# Jacdac_Pressure_Sensor_Maker.net
KiCad netlist of a schematic drawn in EAGLE
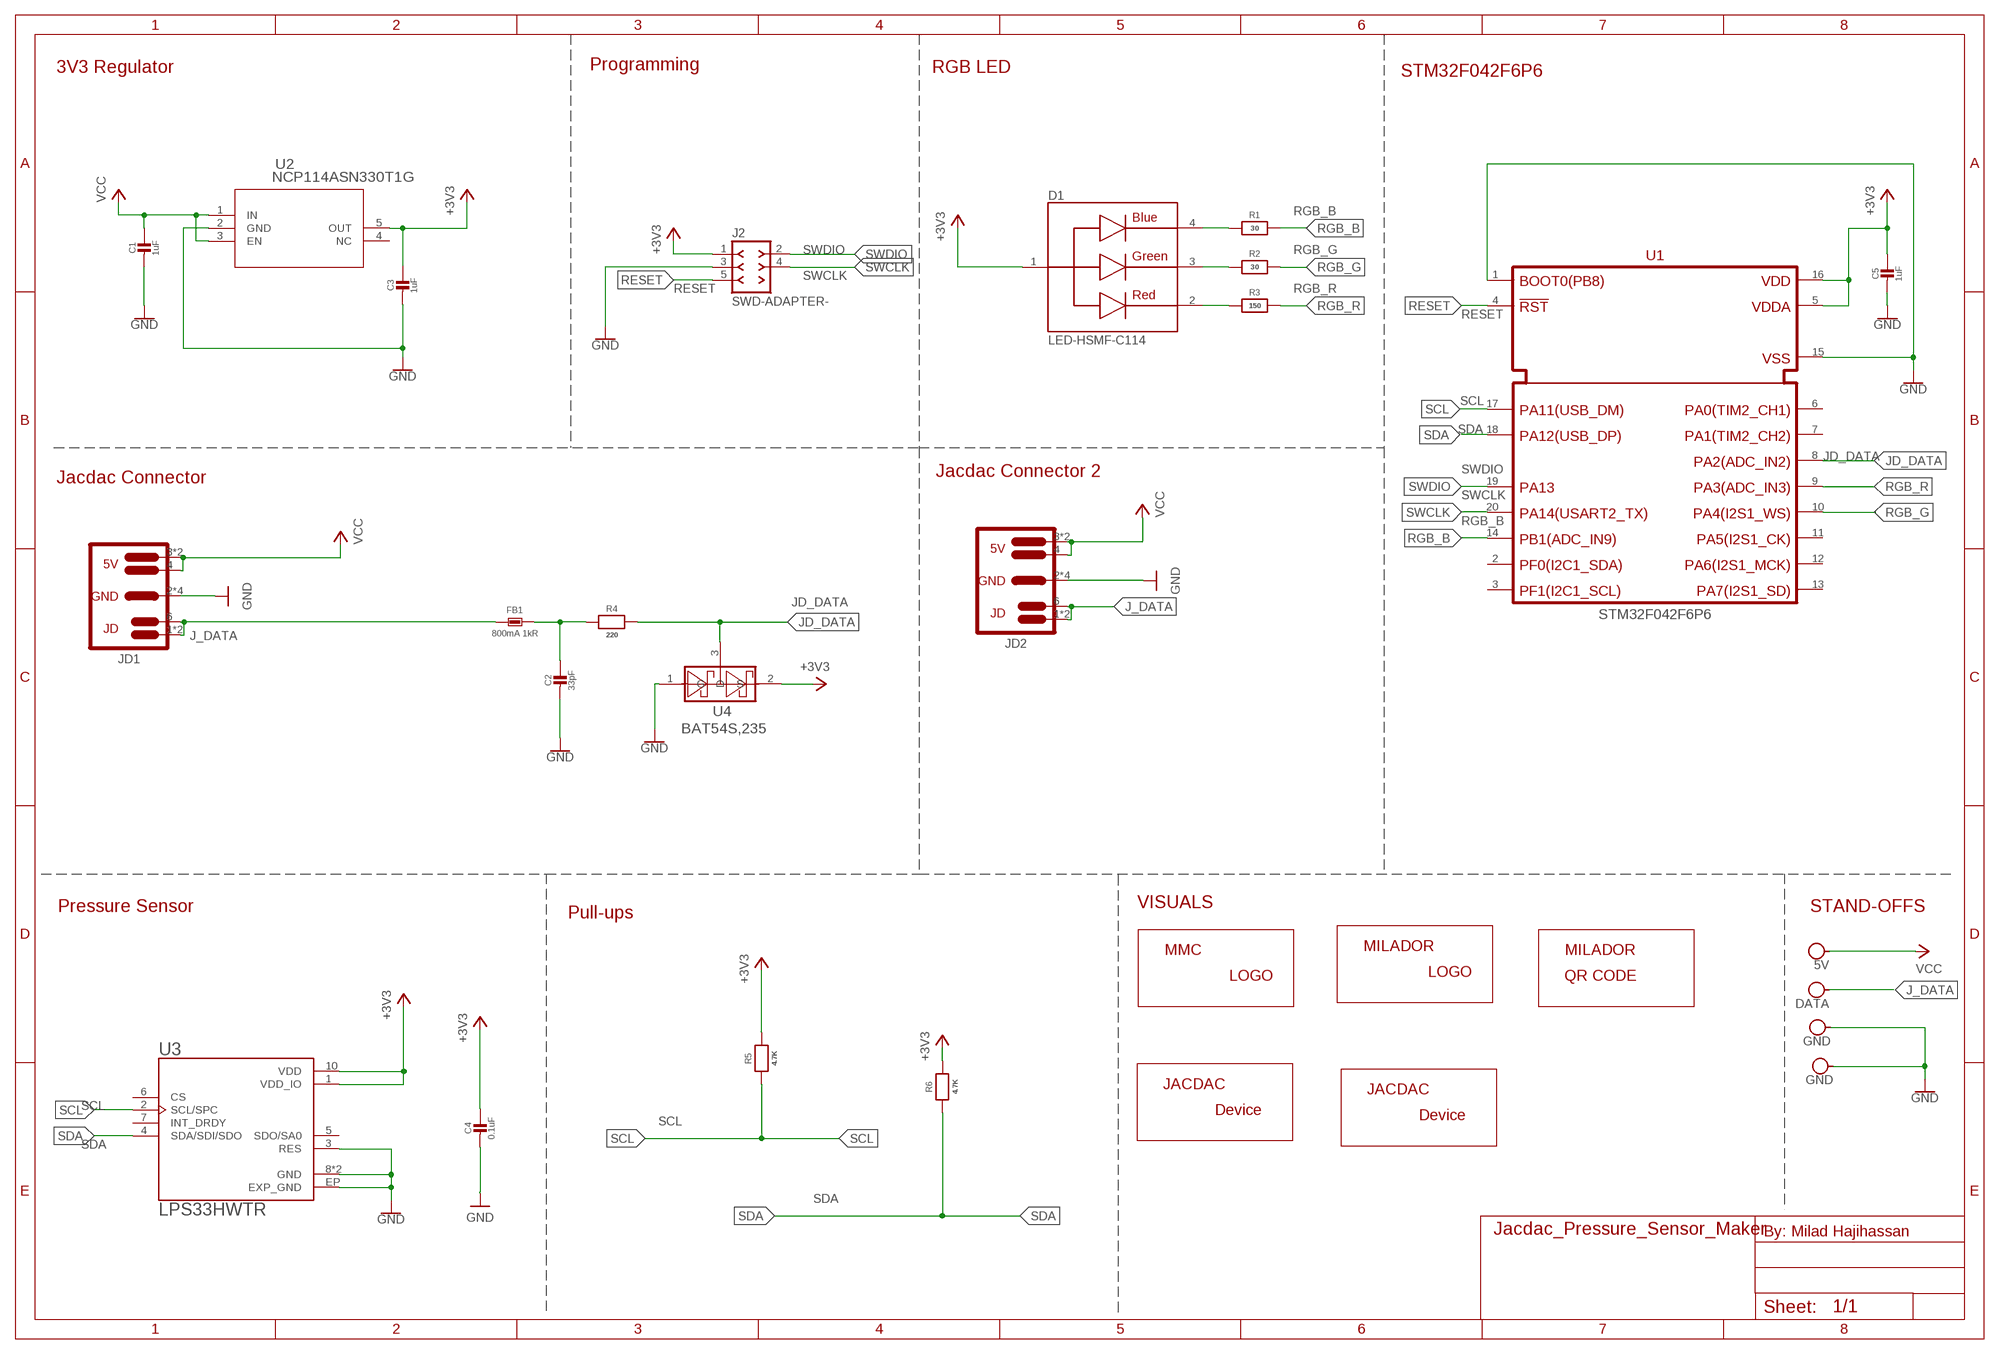
[diagram p0: schematic, sheet 1]

(export (version "E")
  (design (tool "Eeschema 10.0.6"))
  (components
    (comp (ref "C1")
      (value "1uF")
      (footprint "eagle-import:0603-NO")
      (libsource (lib "eagle-import") (part "CAP_CERAMIC-0603-NO"))
    )
    (comp (ref "C2")
      (value "33pF")
      (footprint "eagle-import:0603")
      (libsource (lib "eagle-import") (part "CAP_CERAMIC-0603"))
    )
    (comp (ref "C3")
      (value "1uF")
      (footprint "eagle-import:0603-NO")
      (libsource (lib "eagle-import") (part "CAP_CERAMIC-0603-NO"))
    )
    (comp (ref "C4")
      (value "0.1uF")
      (footprint "eagle-import:0603-NO")
      (libsource (lib "eagle-import") (part "CAP_CERAMIC-0603-NO"))
    )
    (comp (ref "C5")
      (value "1uF")
      (footprint "eagle-import:0603")
      (libsource (lib "eagle-import") (part "CAP_CERAMIC-0603"))
    )
    (comp (ref "D1")
      (value "LED-HSMF-C114")
      (footprint "eagle-import:DIOSC160X150X35-4N")
      (fields (field (name "MF") "Broadcom Limited") (field (name "MP") "HSMF-C114"))
      (libsource (lib "eagle-import") (part "LED-HSMF-C114"))
    )
    (comp (ref "FB1")
      (value "800mA 1kR")
      (footprint "eagle-import:0603-NO")
      (libsource (lib "eagle-import") (part "FERRITE-BEAD-0603-NO"))
    )
    (comp (ref "J2")
      (value "SWD-ADAPTER-")
      (footprint "eagle-import:SWD-ADAPTER")
      (libsource (lib "eagle-import") (part "SWD-ADAPTER-"))
    )
    (comp (ref "J3")
      (value "5V")
      (footprint "eagle-import:M3-HOLE-PWR-OUTL")
      (libsource (lib "eagle-import") (part "JACDAC-M3-PWR-OUTL"))
    )
    (comp (ref "J4")
      (value "DATA")
      (footprint "eagle-import:M3-HOLE-DATA-NOTCH")
      (libsource (lib "eagle-import") (part "JACDAC-M3-DATA-NOTCH"))
    )
    (comp (ref "J5")
      (value "GND")
      (footprint "eagle-import:M3-HOLE-GND")
      (libsource (lib "eagle-import") (part "JACDAC-M3-GND"))
    )
    (comp (ref "J6")
      (value "GND")
      (footprint "eagle-import:M3-HOLE-GND")
      (libsource (lib "eagle-import") (part "JACDAC-M3-GND"))
    )
    (comp (ref "JD1")
      (value "JACDAC-EDGE-OUTIE")
      (footprint "eagle-import:JD-EDGE-OUTIE")
      (libsource (lib "eagle-import") (part "JACDAC-EDGE-OUTIE"))
    )
    (comp (ref "JD2")
      (value "JACDAC-EDGE-OUTIE")
      (footprint "eagle-import:JD-EDGE-OUTIE")
      (libsource (lib "eagle-import") (part "JACDAC-EDGE-OUTIE"))
    )
    (comp (ref "LABEL_JACDAC_PS")
      (value "MILADOR-JACDAC-DEVICE-PS")
      (footprint "eagle-import:JACDAC-PRESSURE-SENSOR")
      (libsource (lib "eagle-import") (part "MILADOR-JACDAC-DEVICE-PS"))
    )
    (comp (ref "LABEL_LPS33HW")
      (value "MILADOR-JACDAC-DEVICE-LPS33HW")
      (footprint "eagle-import:JACDAC-LPS33HW")
      (libsource (lib "eagle-import") (part "MILADOR-JACDAC-DEVICE-LPS33HW"))
    )
    (comp (ref "LABEL_MILADOR")
      (value "MILADOR-LOGO-")
      (footprint "eagle-import:MILADOR_LOGO1")
      (libsource (lib "eagle-import") (part "MILADOR-LOGO-"))
    )
    (comp (ref "LABEL_QR_CODE")
      (value "MILADOR-QR-CODE-JACDAC-GITHUB-PS")
      (footprint "eagle-import:MILADOR_QR_JACDAC_PS")
      (libsource (lib "eagle-import") (part "MILADOR-QR-CODE-JACDAC-GITHUB-PS"))
    )
    (comp (ref "MMC_LOGO")
      (value "MMC_LOGO-XSM")
      (footprint "eagle-import:MMC_X-SMALL_LOGO")
      (libsource (lib "eagle-import") (part "MMC_LOGO-XSM"))
    )
    (comp (ref "R1")
      (value "30")
      (footprint "eagle-import:0603")
      (libsource (lib "eagle-import") (part "RESISTOR-0603"))
    )
    (comp (ref "R2")
      (value "30")
      (footprint "eagle-import:0603")
      (libsource (lib "eagle-import") (part "RESISTOR-0603"))
    )
    (comp (ref "R3")
      (value "150")
      (footprint "eagle-import:0603")
      (libsource (lib "eagle-import") (part "RESISTOR-0603"))
    )
    (comp (ref "R4")
      (value "220")
      (footprint "eagle-import:0603")
      (libsource (lib "eagle-import") (part "RESISTOR-0603"))
    )
    (comp (ref "R5")
      (value "4.7K")
      (footprint "eagle-import:0603")
      (libsource (lib "eagle-import") (part "RESISTOR-0603"))
    )
    (comp (ref "R6")
      (value "4.7K")
      (footprint "eagle-import:0603")
      (libsource (lib "eagle-import") (part "RESISTOR-0603"))
    )
    (comp (ref "U1")
      (value "STM32F042F6P6")
      (footprint "eagle-import:TSSOP20")
      (libsource (lib "eagle-import") (part "STM32F042F6P6"))
    )
    (comp (ref "U2")
      (value "NCP114ASN330T1G")
      (footprint "eagle-import:TSOP-5_ONS")
      (fields (field (name "COPYRIGHT") "Copyright (C) 2021 Ultra Librarian. All rights reserved."))
      (libsource (lib "eagle-import") (part "NCP114ASN330T1G"))
    )
    (comp (ref "U3")
      (value "LPS33HWTR")
      (footprint "eagle-import:PQFN60P330X330X290-11N")
      (fields (field (name "DIGI-KEY_PART_NUMBER") "497-17590-1-ND") (field (name "MF") "STMicroelectronics"))
      (libsource (lib "eagle-import") (part "LPS33HWTR"))
    )
    (comp (ref "U4")
      (value "BAT54S,235")
      (footprint "eagle-import:SOT23-3")
      (fields (field (name "MF") "Diodes") (field (name "MP") "BSS138-7-F"))
      (libsource (lib "eagle-import") (part "BAT54S,235"))
    )
  )
  (nets
    (net (code "1") (name "+3V3") (class "Default")
      (node (ref "C3") (pin "1") (pinfunction "1_1") (pintype "passive"))
      (node (ref "C4") (pin "1") (pinfunction "1_1") (pintype "passive"))
      (node (ref "C5") (pin "1") (pinfunction "1_1") (pintype "passive"))
      (node (ref "D1") (pin "1") (pinfunction "1_1") (pintype "passive"))
      (node (ref "J2") (pin "1") (pinfunction "VCC_1_1") (pintype "passive"))
      (node (ref "R5") (pin "2") (pinfunction "2_2") (pintype "passive"))
      (node (ref "R6") (pin "2") (pinfunction "2_2") (pintype "passive"))
      (node (ref "U1") (pin "16") (pinfunction "VDD_16") (pintype "input"))
      (node (ref "U1") (pin "5") (pinfunction "VDDA_5") (pintype "input"))
      (node (ref "U2") (pin "5") (pinfunction "OUT_5") (pintype "power_in"))
      (node (ref "U3") (pin "1") (pinfunction "VDD_IO_1") (pintype "power_in"))
      (node (ref "U3") (pin "10") (pinfunction "VDD_10") (pintype "power_in"))
      (node (ref "U4") (pin "2") (pinfunction "S_2") (pintype "passive"))
    )
    (net (code "2") (name "GND") (class "Default")
      (node (ref "C1") (pin "2") (pinfunction "2_2") (pintype "passive"))
      (node (ref "C2") (pin "2") (pinfunction "2_2") (pintype "passive"))
      (node (ref "C3") (pin "2") (pinfunction "2_2") (pintype "passive"))
      (node (ref "C4") (pin "2") (pinfunction "2_2") (pintype "passive"))
      (node (ref "C5") (pin "2") (pinfunction "2_2") (pintype "passive"))
      (node (ref "J2") (pin "3") (pinfunction "GND_3_3") (pintype "passive"))
      (node (ref "J5") (pin "H") (pinfunction "P$1_H") (pintype "bidirectional"))
      (node (ref "J6") (pin "H") (pinfunction "P$1_H") (pintype "bidirectional"))
      (node (ref "JD1") (pin "2") (pinfunction "1_2") (pintype "power_in"))
      (node (ref "JD1") (pin "5") (pinfunction "1_5") (pintype "power_in"))
      (node (ref "JD1") (pin "P$2") (pinfunction "1_P$2") (pintype "power_in"))
      (node (ref "JD1") (pin "P$4") (pinfunction "1_P$4") (pintype "power_in"))
      (node (ref "JD2") (pin "2") (pinfunction "1_2") (pintype "power_in"))
      (node (ref "JD2") (pin "5") (pinfunction "1_5") (pintype "power_in"))
      (node (ref "JD2") (pin "P$2") (pinfunction "1_P$2") (pintype "power_in"))
      (node (ref "JD2") (pin "P$4") (pinfunction "1_P$4") (pintype "power_in"))
      (node (ref "U1") (pin "1") (pinfunction "BOOT0_1") (pintype "input"))
      (node (ref "U1") (pin "15") (pinfunction "VSS_15") (pintype "input"))
      (node (ref "U2") (pin "2") (pinfunction "GND_2") (pintype "passive"))
      (node (ref "U3") (pin "3") (pinfunction "RES_3") (pintype "passive"))
      (node (ref "U3") (pin "8") (pinfunction "GND_8") (pintype "power_in"))
      (node (ref "U3") (pin "9") (pinfunction "GND_9") (pintype "power_in"))
      (node (ref "U3") (pin "EP") (pinfunction "EXP_GND_EP") (pintype "power_in"))
      (node (ref "U4") (pin "1") (pinfunction "G_1") (pintype "passive"))
    )
    (net (code "3") (name "JD_DATA") (class "Default")
      (node (ref "R4") (pin "2") (pinfunction "2_2") (pintype "passive"))
      (node (ref "U1") (pin "8") (pinfunction "PA2_8") (pintype "bidirectional"))
      (node (ref "U4") (pin "3") (pinfunction "D_3") (pintype "passive"))
    )
    (net (code "4") (name "J_DATA") (class "Default")
      (node (ref "FB1") (pin "2") (pinfunction "2_2") (pintype "passive"))
      (node (ref "J4") (pin "H") (pinfunction "P$1_H") (pintype "bidirectional"))
      (node (ref "JD1") (pin "1") (pinfunction "2_1") (pintype "bidirectional"))
      (node (ref "JD1") (pin "6") (pinfunction "6_6") (pintype "bidirectional"))
      (node (ref "JD1") (pin "P$3") (pinfunction "2_P$3") (pintype "bidirectional"))
      (node (ref "JD2") (pin "1") (pinfunction "2_1") (pintype "bidirectional"))
      (node (ref "JD2") (pin "6") (pinfunction "6_6") (pintype "bidirectional"))
      (node (ref "JD2") (pin "P$3") (pinfunction "2_P$3") (pintype "bidirectional"))
    )
    (net (code "5") (name "Net-(C2-Pad1)") (class "Default")
      (node (ref "C2") (pin "1") (pinfunction "1_1") (pintype "passive"))
      (node (ref "FB1") (pin "1") (pinfunction "1_1") (pintype "passive"))
      (node (ref "R4") (pin "1") (pinfunction "1_1") (pintype "passive"))
    )
    (net (code "6") (name "Net-(D1-Pad2)") (class "Default")
      (node (ref "D1") (pin "2") (pinfunction "2_2") (pintype "passive"))
      (node (ref "R3") (pin "1") (pinfunction "1_1") (pintype "passive"))
    )
    (net (code "7") (name "Net-(D1-Pad3)") (class "Default")
      (node (ref "D1") (pin "3") (pinfunction "3_3") (pintype "passive"))
      (node (ref "R2") (pin "1") (pinfunction "1_1") (pintype "passive"))
    )
    (net (code "8") (name "Net-(D1-Pad4)") (class "Default")
      (node (ref "D1") (pin "4") (pinfunction "4_4") (pintype "passive"))
      (node (ref "R1") (pin "1") (pinfunction "1_1") (pintype "passive"))
    )
    (net (code "9") (name "RESET") (class "Default")
      (node (ref "J2") (pin "5") (pinfunction "RESET_5_5") (pintype "passive"))
      (node (ref "U1") (pin "4") (pinfunction "~{RST}_4") (pintype "input"))
    )
    (net (code "10") (name "RGB_B") (class "Default")
      (node (ref "R1") (pin "2") (pinfunction "2_2") (pintype "passive"))
      (node (ref "U1") (pin "14") (pinfunction "PB1_14") (pintype "bidirectional"))
    )
    (net (code "11") (name "RGB_G") (class "Default")
      (node (ref "R2") (pin "2") (pinfunction "2_2") (pintype "passive"))
      (node (ref "U1") (pin "10") (pinfunction "PA4_10") (pintype "bidirectional"))
    )
    (net (code "12") (name "RGB_R") (class "Default")
      (node (ref "R3") (pin "2") (pinfunction "2_2") (pintype "passive"))
      (node (ref "U1") (pin "9") (pinfunction "PA3_9") (pintype "bidirectional"))
    )
    (net (code "13") (name "SCL") (class "Default")
      (node (ref "R5") (pin "1") (pinfunction "1_1") (pintype "passive"))
      (node (ref "U1") (pin "17") (pinfunction "PA11_17") (pintype "bidirectional"))
      (node (ref "U3") (pin "2") (pinfunction "SCL/SPC_2") (pintype "input"))
    )
    (net (code "14") (name "SDA") (class "Default")
      (node (ref "R6") (pin "1") (pinfunction "1_1") (pintype "passive"))
      (node (ref "U1") (pin "18") (pinfunction "PA12_18") (pintype "bidirectional"))
      (node (ref "U3") (pin "4") (pinfunction "SDA/SDI/SDO_4") (pintype "bidirectional"))
    )
    (net (code "15") (name "SWCLK") (class "Default")
      (node (ref "J2") (pin "4") (pinfunction "SWCLK_4_4") (pintype "passive"))
      (node (ref "U1") (pin "20") (pinfunction "PA14_20") (pintype "bidirectional"))
    )
    (net (code "16") (name "SWDIO") (class "Default")
      (node (ref "J2") (pin "2") (pinfunction "SWDIO_2_2") (pintype "passive"))
      (node (ref "U1") (pin "19") (pinfunction "PA13_19") (pintype "bidirectional"))
    )
    (net (code "17") (name "VCC") (class "Default")
      (node (ref "C1") (pin "1") (pinfunction "1_1") (pintype "passive"))
      (node (ref "J3") (pin "H") (pinfunction "P$1_H") (pintype "bidirectional"))
      (node (ref "JD1") (pin "3") (pinfunction "3_3") (pintype "power_in"))
      (node (ref "JD1") (pin "4") (pinfunction "4_4") (pintype "power_in"))
      (node (ref "JD1") (pin "P$1") (pinfunction "3_P$1") (pintype "power_in"))
      (node (ref "JD2") (pin "3") (pinfunction "3_3") (pintype "power_in"))
      (node (ref "JD2") (pin "4") (pinfunction "4_4") (pintype "power_in"))
      (node (ref "JD2") (pin "P$1") (pinfunction "3_P$1") (pintype "power_in"))
      (node (ref "U2") (pin "1") (pinfunction "IN_1") (pintype "input"))
      (node (ref "U2") (pin "3") (pinfunction "EN_3") (pintype "passive"))
    )
    (net (code "18") (name "unconnected-(U1-PA0-Pad6)") (class "Default")
      (node (ref "U1") (pin "6") (pinfunction "PA0_6") (pintype "bidirectional"))
    )
    (net (code "19") (name "unconnected-(U1-PA1-Pad7)") (class "Default")
      (node (ref "U1") (pin "7") (pinfunction "PA1_7") (pintype "bidirectional"))
    )
    (net (code "20") (name "unconnected-(U1-PA5-Pad11)") (class "Default")
      (node (ref "U1") (pin "11") (pinfunction "PA5_11") (pintype "bidirectional"))
    )
    (net (code "21") (name "unconnected-(U1-PA6-Pad12)") (class "Default")
      (node (ref "U1") (pin "12") (pinfunction "PA6_12") (pintype "bidirectional"))
    )
    (net (code "22") (name "unconnected-(U1-PA7-Pad13)") (class "Default")
      (node (ref "U1") (pin "13") (pinfunction "PA7_13") (pintype "bidirectional"))
    )
    (net (code "23") (name "unconnected-(U1-PF0-Pad2)") (class "Default")
      (node (ref "U1") (pin "2") (pinfunction "PF0_2") (pintype "bidirectional"))
    )
    (net (code "24") (name "unconnected-(U1-PF1-Pad3)") (class "Default")
      (node (ref "U1") (pin "3") (pinfunction "PF1_3") (pintype "bidirectional"))
    )
    (net (code "25") (name "unconnected-(U2-NC-Pad4)") (class "Default")
      (node (ref "U2") (pin "4") (pinfunction "NC_4") (pintype "no_connect"))
    )
    (net (code "26") (name "unconnected-(U3-CS-Pad6)") (class "Default")
      (node (ref "U3") (pin "6") (pinfunction "CS_6") (pintype "bidirectional"))
    )
    (net (code "27") (name "unconnected-(U3-INT_DRDY-Pad7)") (class "Default")
      (node (ref "U3") (pin "7") (pinfunction "INT_DRDY_7") (pintype "bidirectional"))
    )
    (net (code "28") (name "unconnected-(U3-SDO{slash}SA0-Pad5)") (class "Default")
      (node (ref "U3") (pin "5") (pinfunction "SDO/SA0_5") (pintype "output"))
    )
  )
)
